# FireFaderRev1.net
KiCad netlist of a schematic drawn in EAGLE
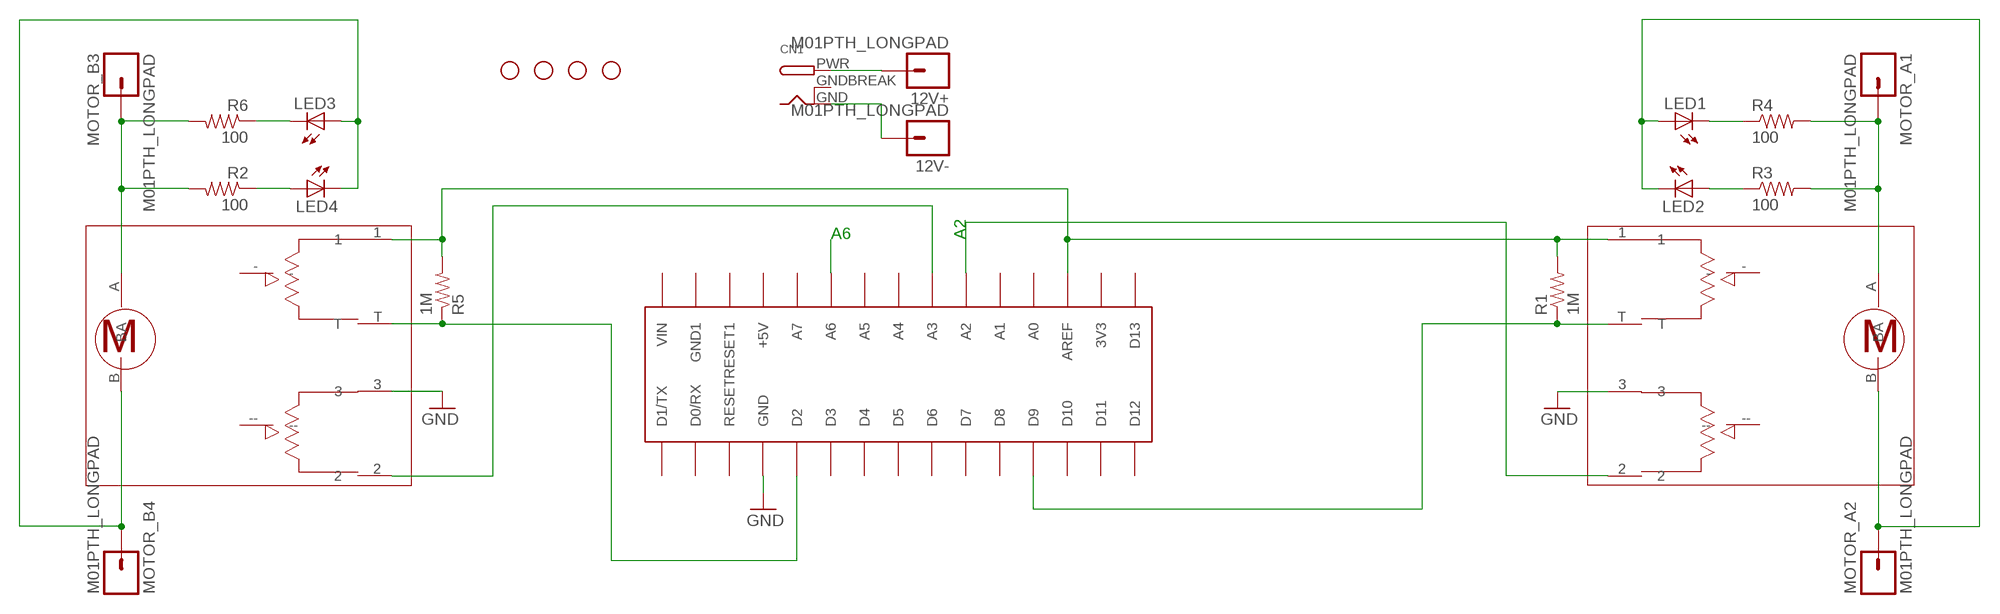
[diagram p0: schematic, sheet 1]

(export (version "E")
  (design (tool "Eeschema 10.0.6"))
  (components
    (comp (ref "12V+")
      (value "M01PTH_LONGPAD")
      (footprint "eagle-import:1X01_LONGPAD")
      (libsource (lib "eagle-import") (part "M01PTH_LONGPAD"))
    )
    (comp (ref "12V-")
      (value "M01PTH_LONGPAD")
      (footprint "eagle-import:1X01_LONGPAD")
      (libsource (lib "eagle-import") (part "M01PTH_LONGPAD"))
    )
    (comp (ref "CN1")
      (value "DCBARRELPTH")
      (footprint "eagle-import:DCJACK_2MM_PTH")
      (libsource (lib "eagle-import") (part "DCBARRELPTH"))
    )
    (comp (ref "LED1")
      (value "LED5MM")
      (footprint "eagle-import:LED5MM")
      (libsource (lib "eagle-import") (part "LED5MM"))
    )
    (comp (ref "LED2")
      (value "LED5MM")
      (footprint "eagle-import:LED5MM")
      (libsource (lib "eagle-import") (part "LED5MM"))
    )
    (comp (ref "LED3")
      (value "LED5MM")
      (footprint "eagle-import:LED5MM")
      (libsource (lib "eagle-import") (part "LED5MM"))
    )
    (comp (ref "LED4")
      (value "LED5MM")
      (footprint "eagle-import:LED5MM")
      (libsource (lib "eagle-import") (part "LED5MM"))
    )
    (comp (ref "MOTOR_A1")
      (value "M01PTH_LONGPAD")
      (footprint "eagle-import:1X01_LONGPAD")
      (libsource (lib "eagle-import") (part "M01PTH_LONGPAD"))
    )
    (comp (ref "MOTOR_A2")
      (value "M01PTH_LONGPAD")
      (footprint "eagle-import:1X01_LONGPAD")
      (libsource (lib "eagle-import") (part "M01PTH_LONGPAD"))
    )
    (comp (ref "MOTOR_B3")
      (value "M01PTH_LONGPAD")
      (footprint "eagle-import:1X01_LONGPAD")
      (libsource (lib "eagle-import") (part "M01PTH_LONGPAD"))
    )
    (comp (ref "MOTOR_B4")
      (value "M01PTH_LONGPAD")
      (footprint "eagle-import:1X01_LONGPAD")
      (libsource (lib "eagle-import") (part "M01PTH_LONGPAD"))
    )
    (comp (ref "R1")
      (value "1M")
      (footprint "eagle-import:AXIAL-0.4")
      (libsource (lib "eagle-import") (part "RESISTORPTH-1/4W"))
    )
    (comp (ref "R2")
      (value "100")
      (footprint "eagle-import:AXIAL-0.6")
      (libsource (lib "eagle-import") (part "RESISTORPTH-1W"))
    )
    (comp (ref "R3")
      (value "100")
      (footprint "eagle-import:AXIAL-0.6")
      (libsource (lib "eagle-import") (part "RESISTORPTH-1W"))
    )
    (comp (ref "R4")
      (value "100")
      (footprint "eagle-import:AXIAL-0.6")
      (libsource (lib "eagle-import") (part "RESISTORPTH-1W"))
    )
    (comp (ref "R5")
      (value "1M")
      (footprint "eagle-import:AXIAL-0.4")
      (libsource (lib "eagle-import") (part "RESISTORPTH-1/4W"))
    )
    (comp (ref "R6")
      (value "100")
      (footprint "eagle-import:AXIAL-0.6")
      (libsource (lib "eagle-import") (part "RESISTORPTH-1W"))
    )
    (comp (ref "STANDOFF1")
      (value "STAND-OFF")
      (footprint "eagle-import:STAND-OFF")
      (libsource (lib "eagle-import") (part "STAND-OFF"))
    )
    (comp (ref "STANDOFF2")
      (value "STAND-OFF")
      (footprint "eagle-import:STAND-OFF")
      (libsource (lib "eagle-import") (part "STAND-OFF"))
    )
    (comp (ref "STANDOFF3")
      (value "STAND-OFF")
      (footprint "eagle-import:STAND-OFF")
      (libsource (lib "eagle-import") (part "STAND-OFF"))
    )
    (comp (ref "STANDOFF4")
      (value "STAND-OFF")
      (footprint "eagle-import:STAND-OFF")
      (libsource (lib "eagle-import") (part "STAND-OFF"))
    )
    (comp (ref "U$1")
      (value "ARDUINONANO")
      (footprint "eagle-import:PDIP-32")
      (libsource (lib "eagle-import") (part "ARDUINONANO"))
    )
    (comp (ref "U$2")
      (value "ALPS-RSA0N11M9A07")
      (footprint "eagle-import:MF-MOTORFADER-ALPS")
      (libsource (lib "eagle-import") (part "ALPS-RSA0N11M9A07"))
    )
    (comp (ref "U$3")
      (value "ALPS-RSA0N11M9A07")
      (footprint "eagle-import:MF-MOTORFADER-ALPS")
      (libsource (lib "eagle-import") (part "ALPS-RSA0N11M9A07"))
    )
  )
  (nets
    (net (code "1") (name "/GNDBREAK") (class "Default")
      (node (ref "CN1") (pin "GNDBREAK") (pinfunction "GNDBREAK_GNDBREAK") (pintype "power_in"))
    )
    (net (code "2") (name "GND") (class "Default")
      (node (ref "U$1") (pin "GND") (pinfunction "GND_GND") (pintype "bidirectional"))
      (node (ref "U$2") (pin "3") (pinfunction "3_3") (pintype "input"))
      (node (ref "U$3") (pin "3") (pinfunction "3_3") (pintype "input"))
    )
    (net (code "3") (name "Net-(12V+-Pad1)") (class "Default")
      (node (ref "12V+") (pin "1") (pinfunction "1_1") (pintype "passive"))
      (node (ref "CN1") (pin "PWR") (pinfunction "PWR_PWR") (pintype "power_in"))
    )
    (net (code "4") (name "Net-(12V--Pad1)") (class "Default")
      (node (ref "12V-") (pin "1") (pinfunction "1_1") (pintype "passive"))
      (node (ref "CN1") (pin "GND") (pinfunction "GND_GND") (pintype "power_in"))
    )
    (net (code "5") (name "Net-(LED1-C)") (class "Default")
      (node (ref "LED1") (pin "K") (pinfunction "C_K") (pintype "passive"))
      (node (ref "R4") (pin "P$1") (pinfunction "1_P$1") (pintype "passive"))
    )
    (net (code "6") (name "Net-(LED2-C)") (class "Default")
      (node (ref "LED1") (pin "A") (pinfunction "A_A") (pintype "passive"))
      (node (ref "LED2") (pin "K") (pinfunction "C_K") (pintype "passive"))
      (node (ref "MOTOR_A2") (pin "1") (pinfunction "1_1") (pintype "passive"))
      (node (ref "U$2") (pin "B") (pinfunction "B_B") (pintype "input"))
    )
    (net (code "7") (name "Net-(LED3-C)") (class "Default")
      (node (ref "LED3") (pin "K") (pinfunction "C_K") (pintype "passive"))
      (node (ref "R6") (pin "P$1") (pinfunction "1_P$1") (pintype "passive"))
    )
    (net (code "8") (name "Net-(LED4-C)") (class "Default")
      (node (ref "LED3") (pin "A") (pinfunction "A_A") (pintype "passive"))
      (node (ref "LED4") (pin "K") (pinfunction "C_K") (pintype "passive"))
      (node (ref "MOTOR_B4") (pin "1") (pinfunction "1_1") (pintype "passive"))
      (node (ref "U$3") (pin "B") (pinfunction "B_B") (pintype "input"))
    )
    (net (code "9") (name "Net-(R1-1)") (class "Default")
      (node (ref "R1") (pin "P$1") (pinfunction "1_P$1") (pintype "passive"))
      (node (ref "U$1") (pin "D9") (pinfunction "D9_D9") (pintype "bidirectional"))
      (node (ref "U$2") (pin "T") (pinfunction "T_T") (pintype "input"))
    )
    (net (code "10") (name "Net-(R1-2)") (class "Default")
      (node (ref "R1") (pin "P$2") (pinfunction "2_P$2") (pintype "passive"))
      (node (ref "R5") (pin "P$2") (pinfunction "2_P$2") (pintype "passive"))
      (node (ref "U$1") (pin "AREF") (pinfunction "AREF_AREF") (pintype "bidirectional"))
      (node (ref "U$2") (pin "1") (pinfunction "1_1") (pintype "input"))
      (node (ref "U$3") (pin "1") (pinfunction "1_1") (pintype "input"))
    )
    (net (code "11") (name "Net-(R2-1)") (class "Default")
      (node (ref "LED4") (pin "A") (pinfunction "A_A") (pintype "passive"))
      (node (ref "R2") (pin "P$1") (pinfunction "1_P$1") (pintype "passive"))
    )
    (net (code "12") (name "Net-(R2-2)") (class "Default")
      (node (ref "MOTOR_B3") (pin "1") (pinfunction "1_1") (pintype "passive"))
      (node (ref "R2") (pin "P$2") (pinfunction "2_P$2") (pintype "passive"))
      (node (ref "R6") (pin "P$2") (pinfunction "2_P$2") (pintype "passive"))
      (node (ref "U$3") (pin "A") (pinfunction "A_A") (pintype "input"))
    )
    (net (code "13") (name "Net-(R3-1)") (class "Default")
      (node (ref "LED2") (pin "A") (pinfunction "A_A") (pintype "passive"))
      (node (ref "R3") (pin "P$1") (pinfunction "1_P$1") (pintype "passive"))
    )
    (net (code "14") (name "Net-(R3-2)") (class "Default")
      (node (ref "MOTOR_A1") (pin "1") (pinfunction "1_1") (pintype "passive"))
      (node (ref "R3") (pin "P$2") (pinfunction "2_P$2") (pintype "passive"))
      (node (ref "R4") (pin "P$2") (pinfunction "2_P$2") (pintype "passive"))
      (node (ref "U$2") (pin "A") (pinfunction "A_A") (pintype "input"))
    )
    (net (code "15") (name "Net-(R5-1)") (class "Default")
      (node (ref "R5") (pin "P$1") (pinfunction "1_P$1") (pintype "passive"))
      (node (ref "U$1") (pin "D2") (pinfunction "D2_D2") (pintype "bidirectional"))
      (node (ref "U$3") (pin "T") (pinfunction "T_T") (pintype "input"))
    )
    (net (code "16") (name "Net-(U$1-PadA2)") (class "Default")
      (node (ref "U$1") (pin "A2") (pinfunction "A2_A2") (pintype "bidirectional"))
      (node (ref "U$2") (pin "2") (pinfunction "2_2") (pintype "input"))
    )
    (net (code "17") (name "Net-(U$1-PadA3)") (class "Default")
      (node (ref "U$1") (pin "A3") (pinfunction "A3_A3") (pintype "bidirectional"))
      (node (ref "U$3") (pin "2") (pinfunction "2_2") (pintype "input"))
    )
    (net (code "18") (name "unconnected-(U$1-Pad+5V)") (class "Default")
      (node (ref "U$1") (pin "+5V") (pinfunction "+5V_+5V") (pintype "bidirectional"))
    )
    (net (code "19") (name "unconnected-(U$1-Pad3V3)") (class "Default")
      (node (ref "U$1") (pin "3V3") (pinfunction "3V3_3V3") (pintype "bidirectional"))
    )
    (net (code "20") (name "unconnected-(U$1-PadA0)") (class "Default")
      (node (ref "U$1") (pin "A0") (pinfunction "A0_A0") (pintype "bidirectional"))
    )
    (net (code "21") (name "unconnected-(U$1-PadA1)") (class "Default")
      (node (ref "U$1") (pin "A1") (pinfunction "A1_A1") (pintype "bidirectional"))
    )
    (net (code "22") (name "unconnected-(U$1-PadA4)") (class "Default")
      (node (ref "U$1") (pin "A4") (pinfunction "A4_A4") (pintype "bidirectional"))
    )
    (net (code "23") (name "unconnected-(U$1-PadA5)") (class "Default")
      (node (ref "U$1") (pin "A5") (pinfunction "A5_A5") (pintype "bidirectional"))
    )
    (net (code "24") (name "unconnected-(U$1-PadA6)") (class "Default")
      (node (ref "U$1") (pin "A6") (pinfunction "A6_A6") (pintype "bidirectional"))
    )
    (net (code "25") (name "unconnected-(U$1-PadA7)") (class "Default")
      (node (ref "U$1") (pin "A7") (pinfunction "A7_A7") (pintype "bidirectional"))
    )
    (net (code "26") (name "unconnected-(U$1-PadD0{slash}RX)") (class "Default")
      (node (ref "U$1") (pin "D0/RX") (pinfunction "D0/RX_D0/RX") (pintype "bidirectional"))
    )
    (net (code "27") (name "unconnected-(U$1-PadD1{slash}TX)") (class "Default")
      (node (ref "U$1") (pin "D1/TX") (pinfunction "D1/TX_D1/TX") (pintype "bidirectional"))
    )
    (net (code "28") (name "unconnected-(U$1-PadD3)") (class "Default")
      (node (ref "U$1") (pin "D3") (pinfunction "D3_D3") (pintype "bidirectional"))
    )
    (net (code "29") (name "unconnected-(U$1-PadD4)") (class "Default")
      (node (ref "U$1") (pin "D4") (pinfunction "D4_D4") (pintype "bidirectional"))
    )
    (net (code "30") (name "unconnected-(U$1-PadD5)") (class "Default")
      (node (ref "U$1") (pin "D5") (pinfunction "D5_D5") (pintype "bidirectional"))
    )
    (net (code "31") (name "unconnected-(U$1-PadD6)") (class "Default")
      (node (ref "U$1") (pin "D6") (pinfunction "D6_D6") (pintype "bidirectional"))
    )
    (net (code "32") (name "unconnected-(U$1-PadD7)") (class "Default")
      (node (ref "U$1") (pin "D7") (pinfunction "D7_D7") (pintype "bidirectional"))
    )
    (net (code "33") (name "unconnected-(U$1-PadD8)") (class "Default")
      (node (ref "U$1") (pin "D8") (pinfunction "D8_D8") (pintype "bidirectional"))
    )
    (net (code "34") (name "unconnected-(U$1-PadD10)") (class "Default")
      (node (ref "U$1") (pin "D10") (pinfunction "D10_D10") (pintype "bidirectional"))
    )
    (net (code "35") (name "unconnected-(U$1-PadD11)") (class "Default")
      (node (ref "U$1") (pin "D11") (pinfunction "D11_D11") (pintype "bidirectional"))
    )
    (net (code "36") (name "unconnected-(U$1-PadD12)") (class "Default")
      (node (ref "U$1") (pin "D12") (pinfunction "D12_D12") (pintype "bidirectional"))
    )
    (net (code "37") (name "unconnected-(U$1-PadD13)") (class "Default")
      (node (ref "U$1") (pin "D13") (pinfunction "D13_D13") (pintype "bidirectional"))
    )
    (net (code "38") (name "unconnected-(U$1-PadGND1)") (class "Default")
      (node (ref "U$1") (pin "GND1") (pinfunction "GND1_GND1") (pintype "bidirectional"))
    )
    (net (code "39") (name "unconnected-(U$1-PadRESET)") (class "Default")
      (node (ref "U$1") (pin "RESET") (pinfunction "RESET_RESET") (pintype "bidirectional"))
    )
    (net (code "40") (name "unconnected-(U$1-PadRESET1)") (class "Default")
      (node (ref "U$1") (pin "RESET1") (pinfunction "RESET1_RESET1") (pintype "bidirectional"))
    )
    (net (code "41") (name "unconnected-(U$1-PadVIN)") (class "Default")
      (node (ref "U$1") (pin "VIN") (pinfunction "VIN_VIN") (pintype "bidirectional"))
    )
    (net (code "42") (name "unconnected-(U$2-Pad-)") (class "Default")
      (node (ref "U$2") (pin "-") (pinfunction "-_-") (pintype "output"))
    )
    (net (code "43") (name "unconnected-(U$2-Pad--)") (class "Default")
      (node (ref "U$2") (pin "--") (pinfunction "--_--") (pintype "output"))
    )
    (net (code "44") (name "unconnected-(U$3-Pad-)") (class "Default")
      (node (ref "U$3") (pin "-") (pinfunction "-_-") (pintype "output"))
    )
    (net (code "45") (name "unconnected-(U$3-Pad--)") (class "Default")
      (node (ref "U$3") (pin "--") (pinfunction "--_--") (pintype "output"))
    )
  )
)
